# single_digit_v1.net
KiCad netlist of a schematic drawn in EAGLE
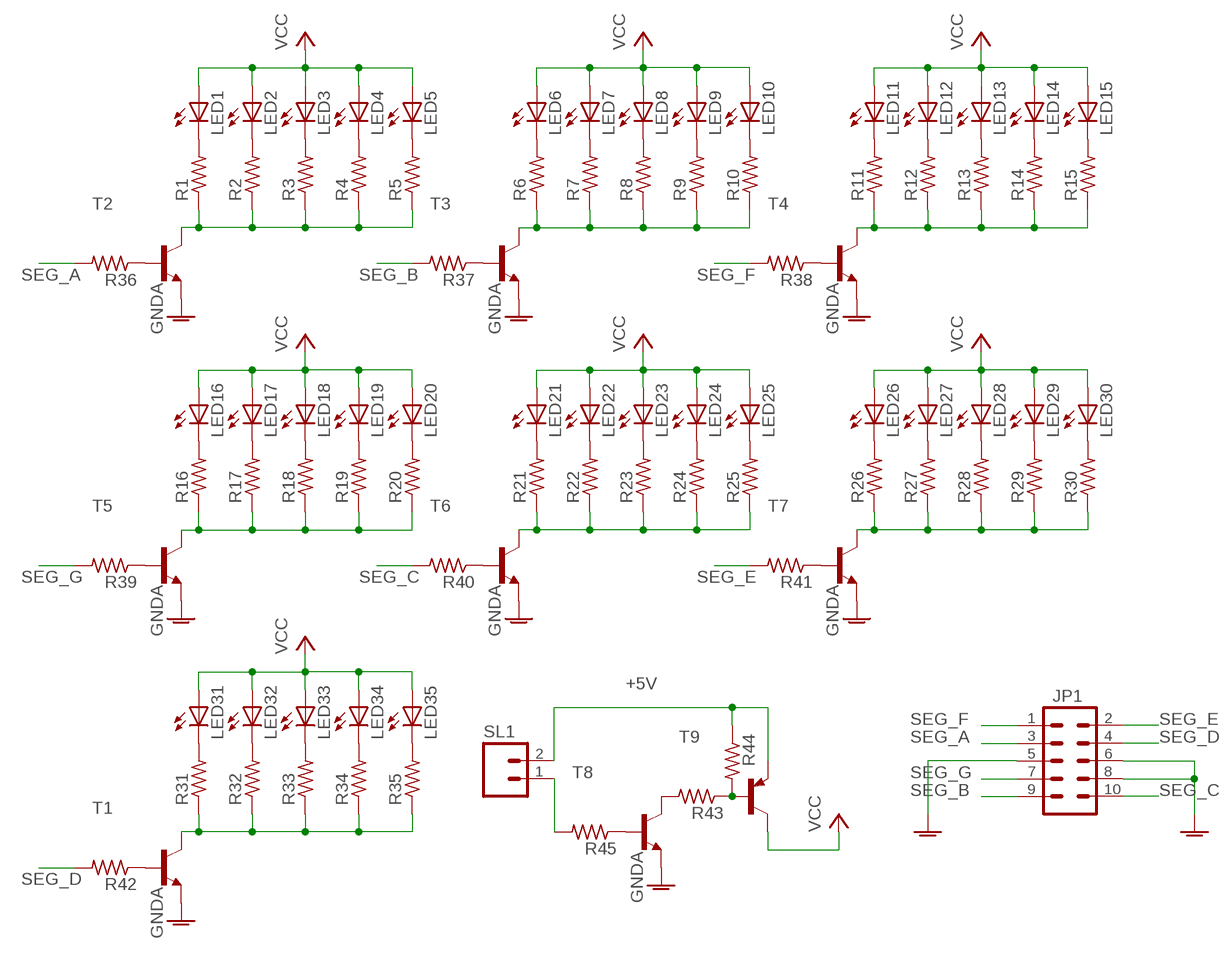
[diagram p0: schematic, sheet 1]

(export (version "E")
  (design (tool "Eeschema 10.0.6"))
  (components
    (comp (ref "JP1")
      (value "M05X2SHD_SMD")
      (footprint "eagle-import:2X5-SHROUDED_SMD")
      (libsource (lib "eagle-import") (part "M05X2SHD_SMD"))
    )
    (comp (ref "LED1")
      (value "LED5MM")
      (footprint "eagle-import:LED5MM")
      (libsource (lib "eagle-import") (part "LED5MM"))
    )
    (comp (ref "LED2")
      (value "LED5MM")
      (footprint "eagle-import:LED5MM")
      (libsource (lib "eagle-import") (part "LED5MM"))
    )
    (comp (ref "LED3")
      (value "LED5MM")
      (footprint "eagle-import:LED5MM")
      (libsource (lib "eagle-import") (part "LED5MM"))
    )
    (comp (ref "LED4")
      (value "LED5MM")
      (footprint "eagle-import:LED5MM")
      (libsource (lib "eagle-import") (part "LED5MM"))
    )
    (comp (ref "LED5")
      (value "LED5MM")
      (footprint "eagle-import:LED5MM")
      (libsource (lib "eagle-import") (part "LED5MM"))
    )
    (comp (ref "LED6")
      (value "LED5MM")
      (footprint "eagle-import:LED5MM")
      (libsource (lib "eagle-import") (part "LED5MM"))
    )
    (comp (ref "LED7")
      (value "LED5MM")
      (footprint "eagle-import:LED5MM")
      (libsource (lib "eagle-import") (part "LED5MM"))
    )
    (comp (ref "LED8")
      (value "LED5MM")
      (footprint "eagle-import:LED5MM")
      (libsource (lib "eagle-import") (part "LED5MM"))
    )
    (comp (ref "LED9")
      (value "LED5MM")
      (footprint "eagle-import:LED5MM")
      (libsource (lib "eagle-import") (part "LED5MM"))
    )
    (comp (ref "LED10")
      (value "LED5MM")
      (footprint "eagle-import:LED5MM")
      (libsource (lib "eagle-import") (part "LED5MM"))
    )
    (comp (ref "LED11")
      (value "LED5MM")
      (footprint "eagle-import:LED5MM")
      (libsource (lib "eagle-import") (part "LED5MM"))
    )
    (comp (ref "LED12")
      (value "LED5MM")
      (footprint "eagle-import:LED5MM")
      (libsource (lib "eagle-import") (part "LED5MM"))
    )
    (comp (ref "LED13")
      (value "LED5MM")
      (footprint "eagle-import:LED5MM")
      (libsource (lib "eagle-import") (part "LED5MM"))
    )
    (comp (ref "LED14")
      (value "LED5MM")
      (footprint "eagle-import:LED5MM")
      (libsource (lib "eagle-import") (part "LED5MM"))
    )
    (comp (ref "LED15")
      (value "LED5MM")
      (footprint "eagle-import:LED5MM")
      (libsource (lib "eagle-import") (part "LED5MM"))
    )
    (comp (ref "LED16")
      (value "LED5MM")
      (footprint "eagle-import:LED5MM")
      (libsource (lib "eagle-import") (part "LED5MM"))
    )
    (comp (ref "LED17")
      (value "LED5MM")
      (footprint "eagle-import:LED5MM")
      (libsource (lib "eagle-import") (part "LED5MM"))
    )
    (comp (ref "LED18")
      (value "LED5MM")
      (footprint "eagle-import:LED5MM")
      (libsource (lib "eagle-import") (part "LED5MM"))
    )
    (comp (ref "LED19")
      (value "LED5MM")
      (footprint "eagle-import:LED5MM")
      (libsource (lib "eagle-import") (part "LED5MM"))
    )
    (comp (ref "LED20")
      (value "LED5MM")
      (footprint "eagle-import:LED5MM")
      (libsource (lib "eagle-import") (part "LED5MM"))
    )
    (comp (ref "LED21")
      (value "LED5MM")
      (footprint "eagle-import:LED5MM")
      (libsource (lib "eagle-import") (part "LED5MM"))
    )
    (comp (ref "LED22")
      (value "LED5MM")
      (footprint "eagle-import:LED5MM")
      (libsource (lib "eagle-import") (part "LED5MM"))
    )
    (comp (ref "LED23")
      (value "LED5MM")
      (footprint "eagle-import:LED5MM")
      (libsource (lib "eagle-import") (part "LED5MM"))
    )
    (comp (ref "LED24")
      (value "LED5MM")
      (footprint "eagle-import:LED5MM")
      (libsource (lib "eagle-import") (part "LED5MM"))
    )
    (comp (ref "LED25")
      (value "LED5MM")
      (footprint "eagle-import:LED5MM")
      (libsource (lib "eagle-import") (part "LED5MM"))
    )
    (comp (ref "LED26")
      (value "LED5MM")
      (footprint "eagle-import:LED5MM")
      (libsource (lib "eagle-import") (part "LED5MM"))
    )
    (comp (ref "LED27")
      (value "LED5MM")
      (footprint "eagle-import:LED5MM")
      (libsource (lib "eagle-import") (part "LED5MM"))
    )
    (comp (ref "LED28")
      (value "LED5MM")
      (footprint "eagle-import:LED5MM")
      (libsource (lib "eagle-import") (part "LED5MM"))
    )
    (comp (ref "LED29")
      (value "LED5MM")
      (footprint "eagle-import:LED5MM")
      (libsource (lib "eagle-import") (part "LED5MM"))
    )
    (comp (ref "LED30")
      (value "LED5MM")
      (footprint "eagle-import:LED5MM")
      (libsource (lib "eagle-import") (part "LED5MM"))
    )
    (comp (ref "LED31")
      (value "LED5MM")
      (footprint "eagle-import:LED5MM")
      (libsource (lib "eagle-import") (part "LED5MM"))
    )
    (comp (ref "LED32")
      (value "LED5MM")
      (footprint "eagle-import:LED5MM")
      (libsource (lib "eagle-import") (part "LED5MM"))
    )
    (comp (ref "LED33")
      (value "LED5MM")
      (footprint "eagle-import:LED5MM")
      (libsource (lib "eagle-import") (part "LED5MM"))
    )
    (comp (ref "LED34")
      (value "LED5MM")
      (footprint "eagle-import:LED5MM")
      (libsource (lib "eagle-import") (part "LED5MM"))
    )
    (comp (ref "LED35")
      (value "LED5MM")
      (footprint "eagle-import:LED5MM")
      (libsource (lib "eagle-import") (part "LED5MM"))
    )
    (comp (ref "R1")
      (value "R-US_M0805")
      (footprint "eagle-import:M0805")
      (libsource (lib "eagle-import") (part "R-US_M0805"))
    )
    (comp (ref "R2")
      (value "R-US_M0805")
      (footprint "eagle-import:M0805")
      (libsource (lib "eagle-import") (part "R-US_M0805"))
    )
    (comp (ref "R3")
      (value "R-US_M0805")
      (footprint "eagle-import:M0805")
      (libsource (lib "eagle-import") (part "R-US_M0805"))
    )
    (comp (ref "R4")
      (value "R-US_M0805")
      (footprint "eagle-import:M0805")
      (libsource (lib "eagle-import") (part "R-US_M0805"))
    )
    (comp (ref "R5")
      (value "R-US_M0805")
      (footprint "eagle-import:M0805")
      (libsource (lib "eagle-import") (part "R-US_M0805"))
    )
    (comp (ref "R6")
      (value "R-US_M0805")
      (footprint "eagle-import:M0805")
      (libsource (lib "eagle-import") (part "R-US_M0805"))
    )
    (comp (ref "R7")
      (value "R-US_M0805")
      (footprint "eagle-import:M0805")
      (libsource (lib "eagle-import") (part "R-US_M0805"))
    )
    (comp (ref "R8")
      (value "R-US_M0805")
      (footprint "eagle-import:M0805")
      (libsource (lib "eagle-import") (part "R-US_M0805"))
    )
    (comp (ref "R9")
      (value "R-US_M0805")
      (footprint "eagle-import:M0805")
      (libsource (lib "eagle-import") (part "R-US_M0805"))
    )
    (comp (ref "R10")
      (value "R-US_M0805")
      (footprint "eagle-import:M0805")
      (libsource (lib "eagle-import") (part "R-US_M0805"))
    )
    (comp (ref "R11")
      (value "R-US_M0805")
      (footprint "eagle-import:M0805")
      (libsource (lib "eagle-import") (part "R-US_M0805"))
    )
    (comp (ref "R12")
      (value "R-US_M0805")
      (footprint "eagle-import:M0805")
      (libsource (lib "eagle-import") (part "R-US_M0805"))
    )
    (comp (ref "R13")
      (value "R-US_M0805")
      (footprint "eagle-import:M0805")
      (libsource (lib "eagle-import") (part "R-US_M0805"))
    )
    (comp (ref "R14")
      (value "R-US_M0805")
      (footprint "eagle-import:M0805")
      (libsource (lib "eagle-import") (part "R-US_M0805"))
    )
    (comp (ref "R15")
      (value "R-US_M0805")
      (footprint "eagle-import:M0805")
      (libsource (lib "eagle-import") (part "R-US_M0805"))
    )
    (comp (ref "R16")
      (value "R-US_M0805")
      (footprint "eagle-import:M0805")
      (libsource (lib "eagle-import") (part "R-US_M0805"))
    )
    (comp (ref "R17")
      (value "R-US_M0805")
      (footprint "eagle-import:M0805")
      (libsource (lib "eagle-import") (part "R-US_M0805"))
    )
    (comp (ref "R18")
      (value "R-US_M0805")
      (footprint "eagle-import:M0805")
      (libsource (lib "eagle-import") (part "R-US_M0805"))
    )
    (comp (ref "R19")
      (value "R-US_M0805")
      (footprint "eagle-import:M0805")
      (libsource (lib "eagle-import") (part "R-US_M0805"))
    )
    (comp (ref "R20")
      (value "R-US_M0805")
      (footprint "eagle-import:M0805")
      (libsource (lib "eagle-import") (part "R-US_M0805"))
    )
    (comp (ref "R21")
      (value "R-US_M0805")
      (footprint "eagle-import:M0805")
      (libsource (lib "eagle-import") (part "R-US_M0805"))
    )
    (comp (ref "R22")
      (value "R-US_M0805")
      (footprint "eagle-import:M0805")
      (libsource (lib "eagle-import") (part "R-US_M0805"))
    )
    (comp (ref "R23")
      (value "R-US_M0805")
      (footprint "eagle-import:M0805")
      (libsource (lib "eagle-import") (part "R-US_M0805"))
    )
    (comp (ref "R24")
      (value "R-US_M0805")
      (footprint "eagle-import:M0805")
      (libsource (lib "eagle-import") (part "R-US_M0805"))
    )
    (comp (ref "R25")
      (value "R-US_M0805")
      (footprint "eagle-import:M0805")
      (libsource (lib "eagle-import") (part "R-US_M0805"))
    )
    (comp (ref "R26")
      (value "R-US_M0805")
      (footprint "eagle-import:M0805")
      (libsource (lib "eagle-import") (part "R-US_M0805"))
    )
    (comp (ref "R27")
      (value "R-US_M0805")
      (footprint "eagle-import:M0805")
      (libsource (lib "eagle-import") (part "R-US_M0805"))
    )
    (comp (ref "R28")
      (value "R-US_M0805")
      (footprint "eagle-import:M0805")
      (libsource (lib "eagle-import") (part "R-US_M0805"))
    )
    (comp (ref "R29")
      (value "R-US_M0805")
      (footprint "eagle-import:M0805")
      (libsource (lib "eagle-import") (part "R-US_M0805"))
    )
    (comp (ref "R30")
      (value "R-US_M0805")
      (footprint "eagle-import:M0805")
      (libsource (lib "eagle-import") (part "R-US_M0805"))
    )
    (comp (ref "R31")
      (value "R-US_M0805")
      (footprint "eagle-import:M0805")
      (libsource (lib "eagle-import") (part "R-US_M0805"))
    )
    (comp (ref "R32")
      (value "R-US_M0805")
      (footprint "eagle-import:M0805")
      (libsource (lib "eagle-import") (part "R-US_M0805"))
    )
    (comp (ref "R33")
      (value "R-US_M0805")
      (footprint "eagle-import:M0805")
      (libsource (lib "eagle-import") (part "R-US_M0805"))
    )
    (comp (ref "R34")
      (value "R-US_M0805")
      (footprint "eagle-import:M0805")
      (libsource (lib "eagle-import") (part "R-US_M0805"))
    )
    (comp (ref "R35")
      (value "R-US_M0805")
      (footprint "eagle-import:M0805")
      (libsource (lib "eagle-import") (part "R-US_M0805"))
    )
    (comp (ref "R36")
      (value "R-US_M0805")
      (footprint "eagle-import:M0805")
      (libsource (lib "eagle-import") (part "R-US_M0805"))
    )
    (comp (ref "R37")
      (value "R-US_M0805")
      (footprint "eagle-import:M0805")
      (libsource (lib "eagle-import") (part "R-US_M0805"))
    )
    (comp (ref "R38")
      (value "R-US_M0805")
      (footprint "eagle-import:M0805")
      (libsource (lib "eagle-import") (part "R-US_M0805"))
    )
    (comp (ref "R39")
      (value "R-US_M0805")
      (footprint "eagle-import:M0805")
      (libsource (lib "eagle-import") (part "R-US_M0805"))
    )
    (comp (ref "R40")
      (value "R-US_M0805")
      (footprint "eagle-import:M0805")
      (libsource (lib "eagle-import") (part "R-US_M0805"))
    )
    (comp (ref "R41")
      (value "R-US_M0805")
      (footprint "eagle-import:M0805")
      (libsource (lib "eagle-import") (part "R-US_M0805"))
    )
    (comp (ref "R42")
      (value "R-US_M0805")
      (footprint "eagle-import:M0805")
      (libsource (lib "eagle-import") (part "R-US_M0805"))
    )
    (comp (ref "R43")
      (value "R-US_M0805")
      (footprint "eagle-import:M0805")
      (libsource (lib "eagle-import") (part "R-US_M0805"))
    )
    (comp (ref "R44")
      (value "R-US_M0805")
      (footprint "eagle-import:M0805")
      (libsource (lib "eagle-import") (part "R-US_M0805"))
    )
    (comp (ref "R45")
      (value "R-US_M0805")
      (footprint "eagle-import:M0805")
      (libsource (lib "eagle-import") (part "R-US_M0805"))
    )
    (comp (ref "SL1")
      (value "M02")
      (footprint "eagle-import:02P")
      (libsource (lib "eagle-import") (part "M02"))
    )
    (comp (ref "T1")
      (value "MMBT2222ALT1-NPN-SOT23-BEC")
      (footprint "eagle-import:SOT23-BEC")
      (libsource (lib "eagle-import") (part "-NPN-SOT23-BECMMBT2222ALT1"))
    )
    (comp (ref "T2")
      (value "MMBT2222ALT1-NPN-SOT23-BEC")
      (footprint "eagle-import:SOT23-BEC")
      (libsource (lib "eagle-import") (part "-NPN-SOT23-BECMMBT2222ALT1"))
    )
    (comp (ref "T3")
      (value "MMBT2222ALT1-NPN-SOT23-BEC")
      (footprint "eagle-import:SOT23-BEC")
      (libsource (lib "eagle-import") (part "-NPN-SOT23-BECMMBT2222ALT1"))
    )
    (comp (ref "T4")
      (value "MMBT2222ALT1-NPN-SOT23-BEC")
      (footprint "eagle-import:SOT23-BEC")
      (libsource (lib "eagle-import") (part "-NPN-SOT23-BECMMBT2222ALT1"))
    )
    (comp (ref "T5")
      (value "MMBT2222ALT1-NPN-SOT23-BEC")
      (footprint "eagle-import:SOT23-BEC")
      (libsource (lib "eagle-import") (part "-NPN-SOT23-BECMMBT2222ALT1"))
    )
    (comp (ref "T6")
      (value "MMBT2222ALT1-NPN-SOT23-BEC")
      (footprint "eagle-import:SOT23-BEC")
      (libsource (lib "eagle-import") (part "-NPN-SOT23-BECMMBT2222ALT1"))
    )
    (comp (ref "T7")
      (value "MMBT2222ALT1-NPN-SOT23-BEC")
      (footprint "eagle-import:SOT23-BEC")
      (libsource (lib "eagle-import") (part "-NPN-SOT23-BECMMBT2222ALT1"))
    )
    (comp (ref "T8")
      (value "MMBT2222ALT1-NPN-SOT23-BEC")
      (footprint "eagle-import:SOT23-BEC")
      (libsource (lib "eagle-import") (part "-NPN-SOT23-BECMMBT2222ALT1"))
    )
    (comp (ref "T9")
      (value "MMBT2907ALT1-PNP-SOT23-BEC")
      (footprint "eagle-import:SOT23-BEC")
      (libsource (lib "eagle-import") (part "-PNP-SOT23-BECMMBT2907ALT1"))
    )
  )
  (nets
    (net (code "1") (name "/+5V") (class "Default")
      (node (ref "R44") (pin "1") (pinfunction "1_1") (pintype "passive"))
      (node (ref "SL1") (pin "2") (pinfunction "2_2") (pintype "passive"))
      (node (ref "T9") (pin "E") (pinfunction "E_E") (pintype "passive"))
    )
    (net (code "2") (name "/SEG_A") (class "Default")
      (node (ref "JP1") (pin "3") (pinfunction "3_3") (pintype "passive"))
      (node (ref "R36") (pin "2") (pinfunction "2_2") (pintype "passive"))
    )
    (net (code "3") (name "/SEG_B") (class "Default")
      (node (ref "JP1") (pin "9") (pinfunction "9_9") (pintype "passive"))
      (node (ref "R37") (pin "2") (pinfunction "2_2") (pintype "passive"))
    )
    (net (code "4") (name "/SEG_C") (class "Default")
      (node (ref "JP1") (pin "10") (pinfunction "10_10") (pintype "passive"))
      (node (ref "R40") (pin "2") (pinfunction "2_2") (pintype "passive"))
    )
    (net (code "5") (name "/SEG_D") (class "Default")
      (node (ref "JP1") (pin "4") (pinfunction "4_4") (pintype "passive"))
      (node (ref "R42") (pin "2") (pinfunction "2_2") (pintype "passive"))
    )
    (net (code "6") (name "/SEG_E") (class "Default")
      (node (ref "JP1") (pin "2") (pinfunction "2_2") (pintype "passive"))
      (node (ref "R41") (pin "2") (pinfunction "2_2") (pintype "passive"))
    )
    (net (code "7") (name "/SEG_F") (class "Default")
      (node (ref "JP1") (pin "1") (pinfunction "1_1") (pintype "passive"))
      (node (ref "R38") (pin "2") (pinfunction "2_2") (pintype "passive"))
    )
    (net (code "8") (name "/SEG_G") (class "Default")
      (node (ref "JP1") (pin "7") (pinfunction "7_7") (pintype "passive"))
      (node (ref "R39") (pin "2") (pinfunction "2_2") (pintype "passive"))
    )
    (net (code "9") (name "GNDA") (class "Default")
      (node (ref "JP1") (pin "5") (pinfunction "5_5") (pintype "passive"))
      (node (ref "JP1") (pin "6") (pinfunction "6_6") (pintype "passive"))
      (node (ref "JP1") (pin "8") (pinfunction "8_8") (pintype "passive"))
      (node (ref "T1") (pin "E") (pinfunction "E_E") (pintype "passive"))
      (node (ref "T2") (pin "E") (pinfunction "E_E") (pintype "passive"))
      (node (ref "T3") (pin "E") (pinfunction "E_E") (pintype "passive"))
      (node (ref "T4") (pin "E") (pinfunction "E_E") (pintype "passive"))
      (node (ref "T5") (pin "E") (pinfunction "E_E") (pintype "passive"))
      (node (ref "T6") (pin "E") (pinfunction "E_E") (pintype "passive"))
      (node (ref "T7") (pin "E") (pinfunction "E_E") (pintype "passive"))
      (node (ref "T8") (pin "E") (pinfunction "E_E") (pintype "passive"))
    )
    (net (code "10") (name "Net-(LED1-C)") (class "Default")
      (node (ref "LED1") (pin "K") (pinfunction "C_K") (pintype "passive"))
      (node (ref "R1") (pin "2") (pinfunction "2_2") (pintype "passive"))
    )
    (net (code "11") (name "Net-(LED2-C)") (class "Default")
      (node (ref "LED2") (pin "K") (pinfunction "C_K") (pintype "passive"))
      (node (ref "R2") (pin "2") (pinfunction "2_2") (pintype "passive"))
    )
    (net (code "12") (name "Net-(LED3-C)") (class "Default")
      (node (ref "LED3") (pin "K") (pinfunction "C_K") (pintype "passive"))
      (node (ref "R3") (pin "2") (pinfunction "2_2") (pintype "passive"))
    )
    (net (code "13") (name "Net-(LED4-C)") (class "Default")
      (node (ref "LED4") (pin "K") (pinfunction "C_K") (pintype "passive"))
      (node (ref "R4") (pin "2") (pinfunction "2_2") (pintype "passive"))
    )
    (net (code "14") (name "Net-(LED5-C)") (class "Default")
      (node (ref "LED5") (pin "K") (pinfunction "C_K") (pintype "passive"))
      (node (ref "R5") (pin "2") (pinfunction "2_2") (pintype "passive"))
    )
    (net (code "15") (name "Net-(LED6-C)") (class "Default")
      (node (ref "LED6") (pin "K") (pinfunction "C_K") (pintype "passive"))
      (node (ref "R6") (pin "2") (pinfunction "2_2") (pintype "passive"))
    )
    (net (code "16") (name "Net-(LED7-C)") (class "Default")
      (node (ref "LED7") (pin "K") (pinfunction "C_K") (pintype "passive"))
      (node (ref "R7") (pin "2") (pinfunction "2_2") (pintype "passive"))
    )
    (net (code "17") (name "Net-(LED8-C)") (class "Default")
      (node (ref "LED8") (pin "K") (pinfunction "C_K") (pintype "passive"))
      (node (ref "R8") (pin "2") (pinfunction "2_2") (pintype "passive"))
    )
    (net (code "18") (name "Net-(LED9-C)") (class "Default")
      (node (ref "LED9") (pin "K") (pinfunction "C_K") (pintype "passive"))
      (node (ref "R9") (pin "2") (pinfunction "2_2") (pintype "passive"))
    )
    (net (code "19") (name "Net-(LED10-C)") (class "Default")
      (node (ref "LED10") (pin "K") (pinfunction "C_K") (pintype "passive"))
      (node (ref "R10") (pin "2") (pinfunction "2_2") (pintype "passive"))
    )
    (net (code "20") (name "Net-(LED11-C)") (class "Default")
      (node (ref "LED11") (pin "K") (pinfunction "C_K") (pintype "passive"))
      (node (ref "R11") (pin "2") (pinfunction "2_2") (pintype "passive"))
    )
    (net (code "21") (name "Net-(LED12-C)") (class "Default")
      (node (ref "LED12") (pin "K") (pinfunction "C_K") (pintype "passive"))
      (node (ref "R12") (pin "2") (pinfunction "2_2") (pintype "passive"))
    )
    (net (code "22") (name "Net-(LED13-C)") (class "Default")
      (node (ref "LED13") (pin "K") (pinfunction "C_K") (pintype "passive"))
      (node (ref "R13") (pin "2") (pinfunction "2_2") (pintype "passive"))
    )
    (net (code "23") (name "Net-(LED14-C)") (class "Default")
      (node (ref "LED14") (pin "K") (pinfunction "C_K") (pintype "passive"))
      (node (ref "R14") (pin "2") (pinfunction "2_2") (pintype "passive"))
    )
    (net (code "24") (name "Net-(LED15-C)") (class "Default")
      (node (ref "LED15") (pin "K") (pinfunction "C_K") (pintype "passive"))
      (node (ref "R15") (pin "2") (pinfunction "2_2") (pintype "passive"))
    )
    (net (code "25") (name "Net-(LED16-C)") (class "Default")
      (node (ref "LED16") (pin "K") (pinfunction "C_K") (pintype "passive"))
      (node (ref "R16") (pin "2") (pinfunction "2_2") (pintype "passive"))
    )
    (net (code "26") (name "Net-(LED17-C)") (class "Default")
      (node (ref "LED17") (pin "K") (pinfunction "C_K") (pintype "passive"))
      (node (ref "R17") (pin "2") (pinfunction "2_2") (pintype "passive"))
    )
    (net (code "27") (name "Net-(LED18-C)") (class "Default")
      (node (ref "LED18") (pin "K") (pinfunction "C_K") (pintype "passive"))
      (node (ref "R18") (pin "2") (pinfunction "2_2") (pintype "passive"))
    )
    (net (code "28") (name "Net-(LED19-C)") (class "Default")
      (node (ref "LED19") (pin "K") (pinfunction "C_K") (pintype "passive"))
      (node (ref "R19") (pin "2") (pinfunction "2_2") (pintype "passive"))
    )
    (net (code "29") (name "Net-(LED20-C)") (class "Default")
      (node (ref "LED20") (pin "K") (pinfunction "C_K") (pintype "passive"))
      (node (ref "R20") (pin "2") (pinfunction "2_2") (pintype "passive"))
    )
    (net (code "30") (name "Net-(LED21-C)") (class "Default")
      (node (ref "LED21") (pin "K") (pinfunction "C_K") (pintype "passive"))
      (node (ref "R21") (pin "2") (pinfunction "2_2") (pintype "passive"))
    )
    (net (code "31") (name "Net-(LED22-C)") (class "Default")
      (node (ref "LED22") (pin "K") (pinfunction "C_K") (pintype "passive"))
      (node (ref "R22") (pin "2") (pinfunction "2_2") (pintype "passive"))
    )
    (net (code "32") (name "Net-(LED23-C)") (class "Default")
      (node (ref "LED23") (pin "K") (pinfunction "C_K") (pintype "passive"))
      (node (ref "R23") (pin "2") (pinfunction "2_2") (pintype "passive"))
    )
    (net (code "33") (name "Net-(LED24-C)") (class "Default")
      (node (ref "LED24") (pin "K") (pinfunction "C_K") (pintype "passive"))
      (node (ref "R24") (pin "2") (pinfunction "2_2") (pintype "passive"))
    )
    (net (code "34") (name "Net-(LED25-C)") (class "Default")
      (node (ref "LED25") (pin "K") (pinfunction "C_K") (pintype "passive"))
      (node (ref "R25") (pin "2") (pinfunction "2_2") (pintype "passive"))
    )
    (net (code "35") (name "Net-(LED26-C)") (class "Default")
      (node (ref "LED26") (pin "K") (pinfunction "C_K") (pintype "passive"))
      (node (ref "R26") (pin "2") (pinfunction "2_2") (pintype "passive"))
    )
    (net (code "36") (name "Net-(LED27-C)") (class "Default")
      (node (ref "LED27") (pin "K") (pinfunction "C_K") (pintype "passive"))
      (node (ref "R27") (pin "2") (pinfunction "2_2") (pintype "passive"))
    )
    (net (code "37") (name "Net-(LED28-C)") (class "Default")
      (node (ref "LED28") (pin "K") (pinfunction "C_K") (pintype "passive"))
      (node (ref "R28") (pin "2") (pinfunction "2_2") (pintype "passive"))
    )
    (net (code "38") (name "Net-(LED29-C)") (class "Default")
      (node (ref "LED29") (pin "K") (pinfunction "C_K") (pintype "passive"))
      (node (ref "R29") (pin "2") (pinfunction "2_2") (pintype "passive"))
    )
    (net (code "39") (name "Net-(LED30-C)") (class "Default")
      (node (ref "LED30") (pin "K") (pinfunction "C_K") (pintype "passive"))
      (node (ref "R30") (pin "2") (pinfunction "2_2") (pintype "passive"))
    )
    (net (code "40") (name "Net-(LED31-C)") (class "Default")
      (node (ref "LED31") (pin "K") (pinfunction "C_K") (pintype "passive"))
      (node (ref "R31") (pin "2") (pinfunction "2_2") (pintype "passive"))
    )
    (net (code "41") (name "Net-(LED32-C)") (class "Default")
      (node (ref "LED32") (pin "K") (pinfunction "C_K") (pintype "passive"))
      (node (ref "R32") (pin "2") (pinfunction "2_2") (pintype "passive"))
    )
    (net (code "42") (name "Net-(LED33-C)") (class "Default")
      (node (ref "LED33") (pin "K") (pinfunction "C_K") (pintype "passive"))
      (node (ref "R33") (pin "2") (pinfunction "2_2") (pintype "passive"))
    )
    (net (code "43") (name "Net-(LED34-C)") (class "Default")
      (node (ref "LED34") (pin "K") (pinfunction "C_K") (pintype "passive"))
      (node (ref "R34") (pin "2") (pinfunction "2_2") (pintype "passive"))
    )
    (net (code "44") (name "Net-(LED35-C)") (class "Default")
      (node (ref "LED35") (pin "K") (pinfunction "C_K") (pintype "passive"))
      (node (ref "R35") (pin "2") (pinfunction "2_2") (pintype "passive"))
    )
    (net (code "45") (name "Net-(R1-Pad1)") (class "Default")
      (node (ref "R1") (pin "1") (pinfunction "1_1") (pintype "passive"))
      (node (ref "R2") (pin "1") (pinfunction "1_1") (pintype "passive"))
      (node (ref "R3") (pin "1") (pinfunction "1_1") (pintype "passive"))
      (node (ref "R4") (pin "1") (pinfunction "1_1") (pintype "passive"))
      (node (ref "R5") (pin "1") (pinfunction "1_1") (pintype "passive"))
      (node (ref "T2") (pin "C") (pinfunction "C_C") (pintype "passive"))
    )
    (net (code "46") (name "Net-(R10-Pad1)") (class "Default")
      (node (ref "R10") (pin "1") (pinfunction "1_1") (pintype "passive"))
      (node (ref "R6") (pin "1") (pinfunction "1_1") (pintype "passive"))
      (node (ref "R7") (pin "1") (pinfunction "1_1") (pintype "passive"))
      (node (ref "R8") (pin "1") (pinfunction "1_1") (pintype "passive"))
      (node (ref "R9") (pin "1") (pinfunction "1_1") (pintype "passive"))
      (node (ref "T3") (pin "C") (pinfunction "C_C") (pintype "passive"))
    )
    (net (code "47") (name "Net-(R11-Pad1)") (class "Default")
      (node (ref "R11") (pin "1") (pinfunction "1_1") (pintype "passive"))
      (node (ref "R12") (pin "1") (pinfunction "1_1") (pintype "passive"))
      (node (ref "R13") (pin "1") (pinfunction "1_1") (pintype "passive"))
      (node (ref "R14") (pin "1") (pinfunction "1_1") (pintype "passive"))
      (node (ref "R15") (pin "1") (pinfunction "1_1") (pintype "passive"))
      (node (ref "T4") (pin "C") (pinfunction "C_C") (pintype "passive"))
    )
    (net (code "48") (name "Net-(R16-Pad1)") (class "Default")
      (node (ref "R16") (pin "1") (pinfunction "1_1") (pintype "passive"))
      (node (ref "R17") (pin "1") (pinfunction "1_1") (pintype "passive"))
      (node (ref "R18") (pin "1") (pinfunction "1_1") (pintype "passive"))
      (node (ref "R19") (pin "1") (pinfunction "1_1") (pintype "passive"))
      (node (ref "R20") (pin "1") (pinfunction "1_1") (pintype "passive"))
      (node (ref "T5") (pin "C") (pinfunction "C_C") (pintype "passive"))
    )
    (net (code "49") (name "Net-(R21-Pad1)") (class "Default")
      (node (ref "R21") (pin "1") (pinfunction "1_1") (pintype "passive"))
      (node (ref "R22") (pin "1") (pinfunction "1_1") (pintype "passive"))
      (node (ref "R23") (pin "1") (pinfunction "1_1") (pintype "passive"))
      (node (ref "R24") (pin "1") (pinfunction "1_1") (pintype "passive"))
      (node (ref "R25") (pin "1") (pinfunction "1_1") (pintype "passive"))
      (node (ref "T6") (pin "C") (pinfunction "C_C") (pintype "passive"))
    )
    (net (code "50") (name "Net-(R26-Pad1)") (class "Default")
      (node (ref "R26") (pin "1") (pinfunction "1_1") (pintype "passive"))
      (node (ref "R27") (pin "1") (pinfunction "1_1") (pintype "passive"))
      (node (ref "R28") (pin "1") (pinfunction "1_1") (pintype "passive"))
      (node (ref "R29") (pin "1") (pinfunction "1_1") (pintype "passive"))
      (node (ref "R30") (pin "1") (pinfunction "1_1") (pintype "passive"))
      (node (ref "T7") (pin "C") (pinfunction "C_C") (pintype "passive"))
    )
    (net (code "51") (name "Net-(R31-Pad1)") (class "Default")
      (node (ref "R31") (pin "1") (pinfunction "1_1") (pintype "passive"))
      (node (ref "R32") (pin "1") (pinfunction "1_1") (pintype "passive"))
      (node (ref "R33") (pin "1") (pinfunction "1_1") (pintype "passive"))
      (node (ref "R34") (pin "1") (pinfunction "1_1") (pintype "passive"))
      (node (ref "R35") (pin "1") (pinfunction "1_1") (pintype "passive"))
      (node (ref "T1") (pin "C") (pinfunction "C_C") (pintype "passive"))
    )
    (net (code "52") (name "Net-(R36-Pad1)") (class "Default")
      (node (ref "R36") (pin "1") (pinfunction "1_1") (pintype "passive"))
      (node (ref "T2") (pin "B") (pinfunction "B_B") (pintype "passive"))
    )
    (net (code "53") (name "Net-(R37-Pad1)") (class "Default")
      (node (ref "R37") (pin "1") (pinfunction "1_1") (pintype "passive"))
      (node (ref "T3") (pin "B") (pinfunction "B_B") (pintype "passive"))
    )
    (net (code "54") (name "Net-(R38-Pad1)") (class "Default")
      (node (ref "R38") (pin "1") (pinfunction "1_1") (pintype "passive"))
      (node (ref "T4") (pin "B") (pinfunction "B_B") (pintype "passive"))
    )
    (net (code "55") (name "Net-(R39-Pad1)") (class "Default")
      (node (ref "R39") (pin "1") (pinfunction "1_1") (pintype "passive"))
      (node (ref "T5") (pin "B") (pinfunction "B_B") (pintype "passive"))
    )
    (net (code "56") (name "Net-(R40-Pad1)") (class "Default")
      (node (ref "R40") (pin "1") (pinfunction "1_1") (pintype "passive"))
      (node (ref "T6") (pin "B") (pinfunction "B_B") (pintype "passive"))
    )
    (net (code "57") (name "Net-(R41-Pad1)") (class "Default")
      (node (ref "R41") (pin "1") (pinfunction "1_1") (pintype "passive"))
      (node (ref "T7") (pin "B") (pinfunction "B_B") (pintype "passive"))
    )
    (net (code "58") (name "Net-(R42-Pad1)") (class "Default")
      (node (ref "R42") (pin "1") (pinfunction "1_1") (pintype "passive"))
      (node (ref "T1") (pin "B") (pinfunction "B_B") (pintype "passive"))
    )
    (net (code "59") (name "Net-(R43-Pad1)") (class "Default")
      (node (ref "R43") (pin "1") (pinfunction "1_1") (pintype "passive"))
      (node (ref "R44") (pin "2") (pinfunction "2_2") (pintype "passive"))
      (node (ref "T9") (pin "B") (pinfunction "B_B") (pintype "passive"))
    )
    (net (code "60") (name "Net-(R43-Pad2)") (class "Default")
      (node (ref "R43") (pin "2") (pinfunction "2_2") (pintype "passive"))
      (node (ref "T8") (pin "C") (pinfunction "C_C") (pintype "passive"))
    )
    (net (code "61") (name "Net-(R45-Pad1)") (class "Default")
      (node (ref "R45") (pin "1") (pinfunction "1_1") (pintype "passive"))
      (node (ref "T8") (pin "B") (pinfunction "B_B") (pintype "passive"))
    )
    (net (code "62") (name "Net-(R45-Pad2)") (class "Default")
      (node (ref "R45") (pin "2") (pinfunction "2_2") (pintype "passive"))
      (node (ref "SL1") (pin "1") (pinfunction "1_1") (pintype "passive"))
    )
    (net (code "63") (name "VCC") (class "Default")
      (node (ref "LED1") (pin "A") (pinfunction "A_A") (pintype "passive"))
      (node (ref "LED10") (pin "A") (pinfunction "A_A") (pintype "passive"))
      (node (ref "LED11") (pin "A") (pinfunction "A_A") (pintype "passive"))
      (node (ref "LED12") (pin "A") (pinfunction "A_A") (pintype "passive"))
      (node (ref "LED13") (pin "A") (pinfunction "A_A") (pintype "passive"))
      (node (ref "LED14") (pin "A") (pinfunction "A_A") (pintype "passive"))
      (node (ref "LED15") (pin "A") (pinfunction "A_A") (pintype "passive"))
      (node (ref "LED16") (pin "A") (pinfunction "A_A") (pintype "passive"))
      (node (ref "LED17") (pin "A") (pinfunction "A_A") (pintype "passive"))
      (node (ref "LED18") (pin "A") (pinfunction "A_A") (pintype "passive"))
      (node (ref "LED19") (pin "A") (pinfunction "A_A") (pintype "passive"))
      (node (ref "LED2") (pin "A") (pinfunction "A_A") (pintype "passive"))
      (node (ref "LED20") (pin "A") (pinfunction "A_A") (pintype "passive"))
      (node (ref "LED21") (pin "A") (pinfunction "A_A") (pintype "passive"))
      (node (ref "LED22") (pin "A") (pinfunction "A_A") (pintype "passive"))
      (node (ref "LED23") (pin "A") (pinfunction "A_A") (pintype "passive"))
      (node (ref "LED24") (pin "A") (pinfunction "A_A") (pintype "passive"))
      (node (ref "LED25") (pin "A") (pinfunction "A_A") (pintype "passive"))
      (node (ref "LED26") (pin "A") (pinfunction "A_A") (pintype "passive"))
      (node (ref "LED27") (pin "A") (pinfunction "A_A") (pintype "passive"))
      (node (ref "LED28") (pin "A") (pinfunction "A_A") (pintype "passive"))
      (node (ref "LED29") (pin "A") (pinfunction "A_A") (pintype "passive"))
      (node (ref "LED3") (pin "A") (pinfunction "A_A") (pintype "passive"))
      (node (ref "LED30") (pin "A") (pinfunction "A_A") (pintype "passive"))
      (node (ref "LED31") (pin "A") (pinfunction "A_A") (pintype "passive"))
      (node (ref "LED32") (pin "A") (pinfunction "A_A") (pintype "passive"))
      (node (ref "LED33") (pin "A") (pinfunction "A_A") (pintype "passive"))
      (node (ref "LED34") (pin "A") (pinfunction "A_A") (pintype "passive"))
      (node (ref "LED35") (pin "A") (pinfunction "A_A") (pintype "passive"))
      (node (ref "LED4") (pin "A") (pinfunction "A_A") (pintype "passive"))
      (node (ref "LED5") (pin "A") (pinfunction "A_A") (pintype "passive"))
      (node (ref "LED6") (pin "A") (pinfunction "A_A") (pintype "passive"))
      (node (ref "LED7") (pin "A") (pinfunction "A_A") (pintype "passive"))
      (node (ref "LED8") (pin "A") (pinfunction "A_A") (pintype "passive"))
      (node (ref "LED9") (pin "A") (pinfunction "A_A") (pintype "passive"))
      (node (ref "T9") (pin "C") (pinfunction "C_C") (pintype "passive"))
    )
  )
)
